# Adafruit_Flora_LSM303.net
KiCad netlist of a schematic drawn in EAGLE
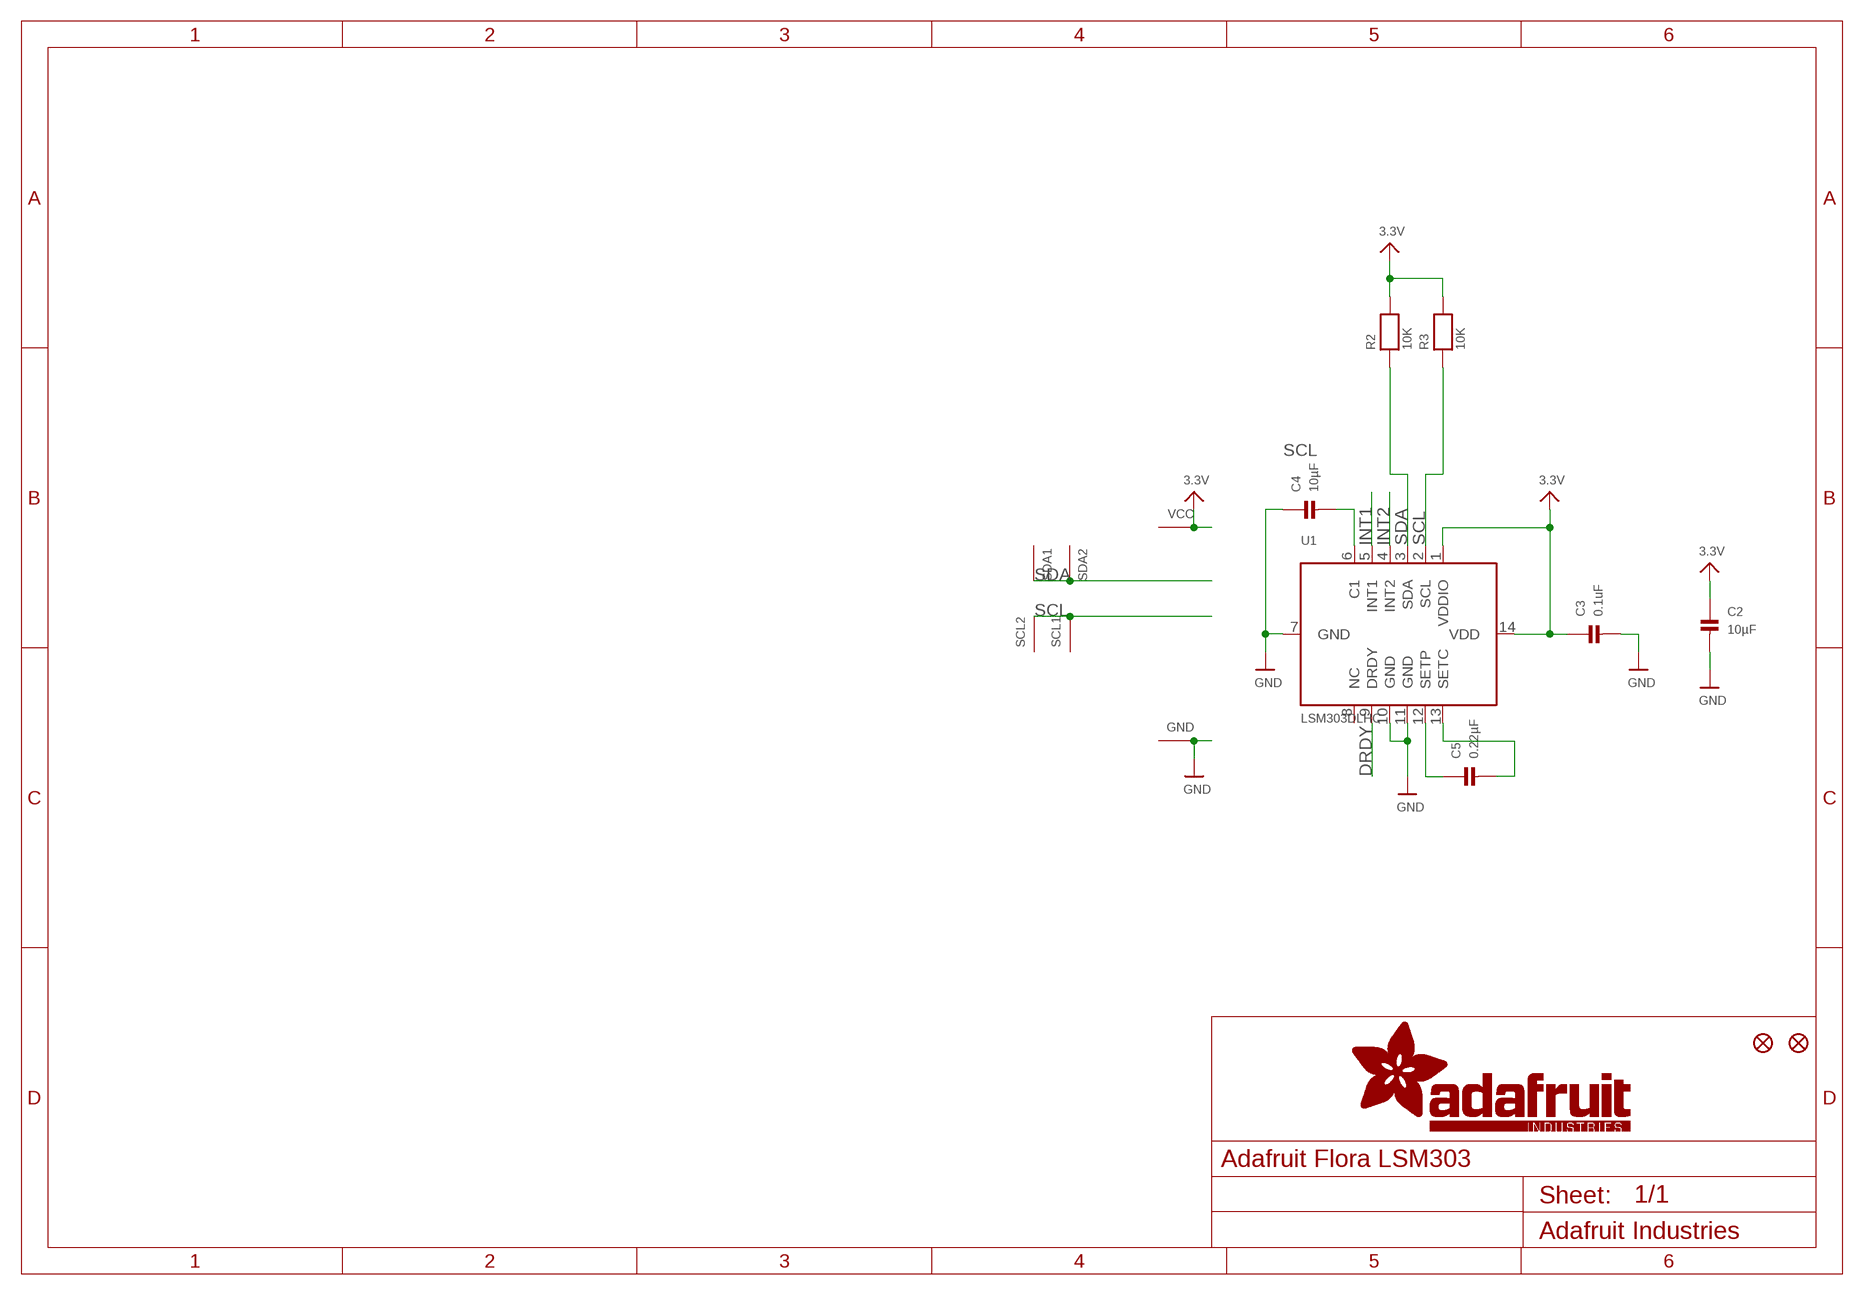
[diagram p0: schematic, sheet 1]

(export (version "E")
  (design (tool "Eeschema 10.0.6"))
  (components
    (comp (ref "C2")
      (value "10µF")
      (footprint "eagle-import:_0805")
      (libsource (lib "eagle-import") (part "CAP_CERAMIC_0805"))
    )
    (comp (ref "C3")
      (value "0.1uF")
      (footprint "eagle-import:_0805")
      (libsource (lib "eagle-import") (part "CAP_CERAMIC_0805"))
    )
    (comp (ref "C4")
      (value "10µF")
      (footprint "eagle-import:_0805")
      (libsource (lib "eagle-import") (part "CAP_CERAMIC_0805"))
    )
    (comp (ref "C5")
      (value "0.22µF")
      (footprint "eagle-import:_0805")
      (libsource (lib "eagle-import") (part "CAP_CERAMIC_0805"))
    )
    (comp (ref "FID1")
      (value "FIDUCIAL\"\"")
      (footprint "eagle-import:FIDUCIAL_1MM")
      (libsource (lib "eagle-import") (part "FIDUCIAL{dblquote}{dblquote}"))
    )
    (comp (ref "FID2")
      (value "FIDUCIAL\"\"")
      (footprint "eagle-import:FIDUCIAL_1MM")
      (libsource (lib "eagle-import") (part "FIDUCIAL{dblquote}{dblquote}"))
    )
    (comp (ref "GND")
      (value "SEWTAP0.5IN")
      (footprint "eagle-import:SEWINGTAP_0.5")
      (libsource (lib "eagle-import") (part "SEWTAP0.5IN"))
    )
    (comp (ref "R2")
      (value "10K")
      (footprint "eagle-import:_0805")
      (libsource (lib "eagle-import") (part "RESISTOR_0805"))
    )
    (comp (ref "R3")
      (value "10K")
      (footprint "eagle-import:_0805")
      (libsource (lib "eagle-import") (part "RESISTOR_0805"))
    )
    (comp (ref "SCL1")
      (value "SEWTAP0.5IN")
      (footprint "eagle-import:SEWINGTAP_0.5")
      (libsource (lib "eagle-import") (part "SEWTAP0.5IN"))
    )
    (comp (ref "SCL2")
      (value "SEWTAP0.5IN")
      (footprint "eagle-import:SEWINGTAP_0.5")
      (libsource (lib "eagle-import") (part "SEWTAP0.5IN"))
    )
    (comp (ref "SDA1")
      (value "SEWTAP0.5IN")
      (footprint "eagle-import:SEWINGTAP_0.5")
      (libsource (lib "eagle-import") (part "SEWTAP0.5IN"))
    )
    (comp (ref "SDA2")
      (value "SEWTAP0.5IN")
      (footprint "eagle-import:SEWINGTAP_0.5")
      (libsource (lib "eagle-import") (part "SEWTAP0.5IN"))
    )
    (comp (ref "U1")
      (value "LSM303DLHC")
      (footprint "eagle-import:LGA14")
      (libsource (lib "eagle-import") (part "LSM303DLHC"))
    )
    (comp (ref "VCC")
      (value "SEWTAP0.5IN")
      (footprint "eagle-import:SEWINGTAP_0.5")
      (libsource (lib "eagle-import") (part "SEWTAP0.5IN"))
    )
  )
  (nets
    (net (code "1") (name "/DRDY") (class "Default")
      (node (ref "U1") (pin "9") (pinfunction "DRDY_9") (pintype "output"))
    )
    (net (code "2") (name "/INT1") (class "Default")
      (node (ref "U1") (pin "5") (pinfunction "INT1_5") (pintype "output"))
    )
    (net (code "3") (name "/INT2") (class "Default")
      (node (ref "U1") (pin "4") (pinfunction "INT2_4") (pintype "output"))
    )
    (net (code "4") (name "/SCL") (class "Default")
      (node (ref "R3") (pin "1") (pinfunction "1_1") (pintype "passive"))
      (node (ref "SCL1") (pin "TAP") (pinfunction "SEW_TAP") (pintype "bidirectional"))
      (node (ref "SCL2") (pin "TAP") (pinfunction "SEW_TAP") (pintype "bidirectional"))
      (node (ref "U1") (pin "2") (pinfunction "SCL_2") (pintype "bidirectional"))
    )
    (net (code "5") (name "/SDA") (class "Default")
      (node (ref "R2") (pin "1") (pinfunction "1_1") (pintype "passive"))
      (node (ref "SDA1") (pin "TAP") (pinfunction "SEW_TAP") (pintype "bidirectional"))
      (node (ref "SDA2") (pin "TAP") (pinfunction "SEW_TAP") (pintype "bidirectional"))
      (node (ref "U1") (pin "3") (pinfunction "SDA_3") (pintype "bidirectional"))
    )
    (net (code "6") (name "3.3V") (class "Default")
      (node (ref "C2") (pin "1") (pinfunction "P$1_1") (pintype "passive"))
      (node (ref "C3") (pin "1") (pinfunction "P$1_1") (pintype "passive"))
      (node (ref "R2") (pin "2") (pinfunction "2_2") (pintype "passive"))
      (node (ref "R3") (pin "2") (pinfunction "2_2") (pintype "passive"))
      (node (ref "U1") (pin "1") (pinfunction "VDDIO_1") (pintype "power_in"))
      (node (ref "U1") (pin "14") (pinfunction "VDD_14") (pintype "power_in"))
      (node (ref "VCC") (pin "TAP") (pinfunction "SEW_TAP") (pintype "bidirectional"))
    )
    (net (code "7") (name "GND") (class "Default")
      (node (ref "C2") (pin "2") (pinfunction "P$2_2") (pintype "passive"))
      (node (ref "C3") (pin "2") (pinfunction "P$2_2") (pintype "passive"))
      (node (ref "C4") (pin "1") (pinfunction "P$1_1") (pintype "passive"))
      (node (ref "GND") (pin "TAP") (pinfunction "SEW_TAP") (pintype "bidirectional"))
      (node (ref "U1") (pin "10") (pinfunction "GND_10") (pintype "power_in"))
      (node (ref "U1") (pin "11") (pinfunction "GND_11") (pintype "power_in"))
      (node (ref "U1") (pin "7") (pinfunction "GND_7") (pintype "power_in"))
    )
    (net (code "8") (name "Net-(C4-P$2)") (class "Default")
      (node (ref "C4") (pin "2") (pinfunction "P$2_2") (pintype "passive"))
      (node (ref "U1") (pin "6") (pinfunction "C1_6") (pintype "bidirectional"))
    )
    (net (code "9") (name "Net-(C5-P$1)") (class "Default")
      (node (ref "C5") (pin "1") (pinfunction "P$1_1") (pintype "passive"))
      (node (ref "U1") (pin "12") (pinfunction "SETP_12") (pintype "bidirectional"))
    )
    (net (code "10") (name "Net-(C5-P$2)") (class "Default")
      (node (ref "C5") (pin "2") (pinfunction "P$2_2") (pintype "passive"))
      (node (ref "U1") (pin "13") (pinfunction "SETC_13") (pintype "bidirectional"))
    )
    (net (code "11") (name "unconnected-(U1-NC-Pad8)") (class "Default")
      (node (ref "U1") (pin "8") (pinfunction "NC_8") (pintype "bidirectional"))
    )
  )
)
